# 2-MCU.net
KiCad netlist of a schematic drawn in Altium Designer
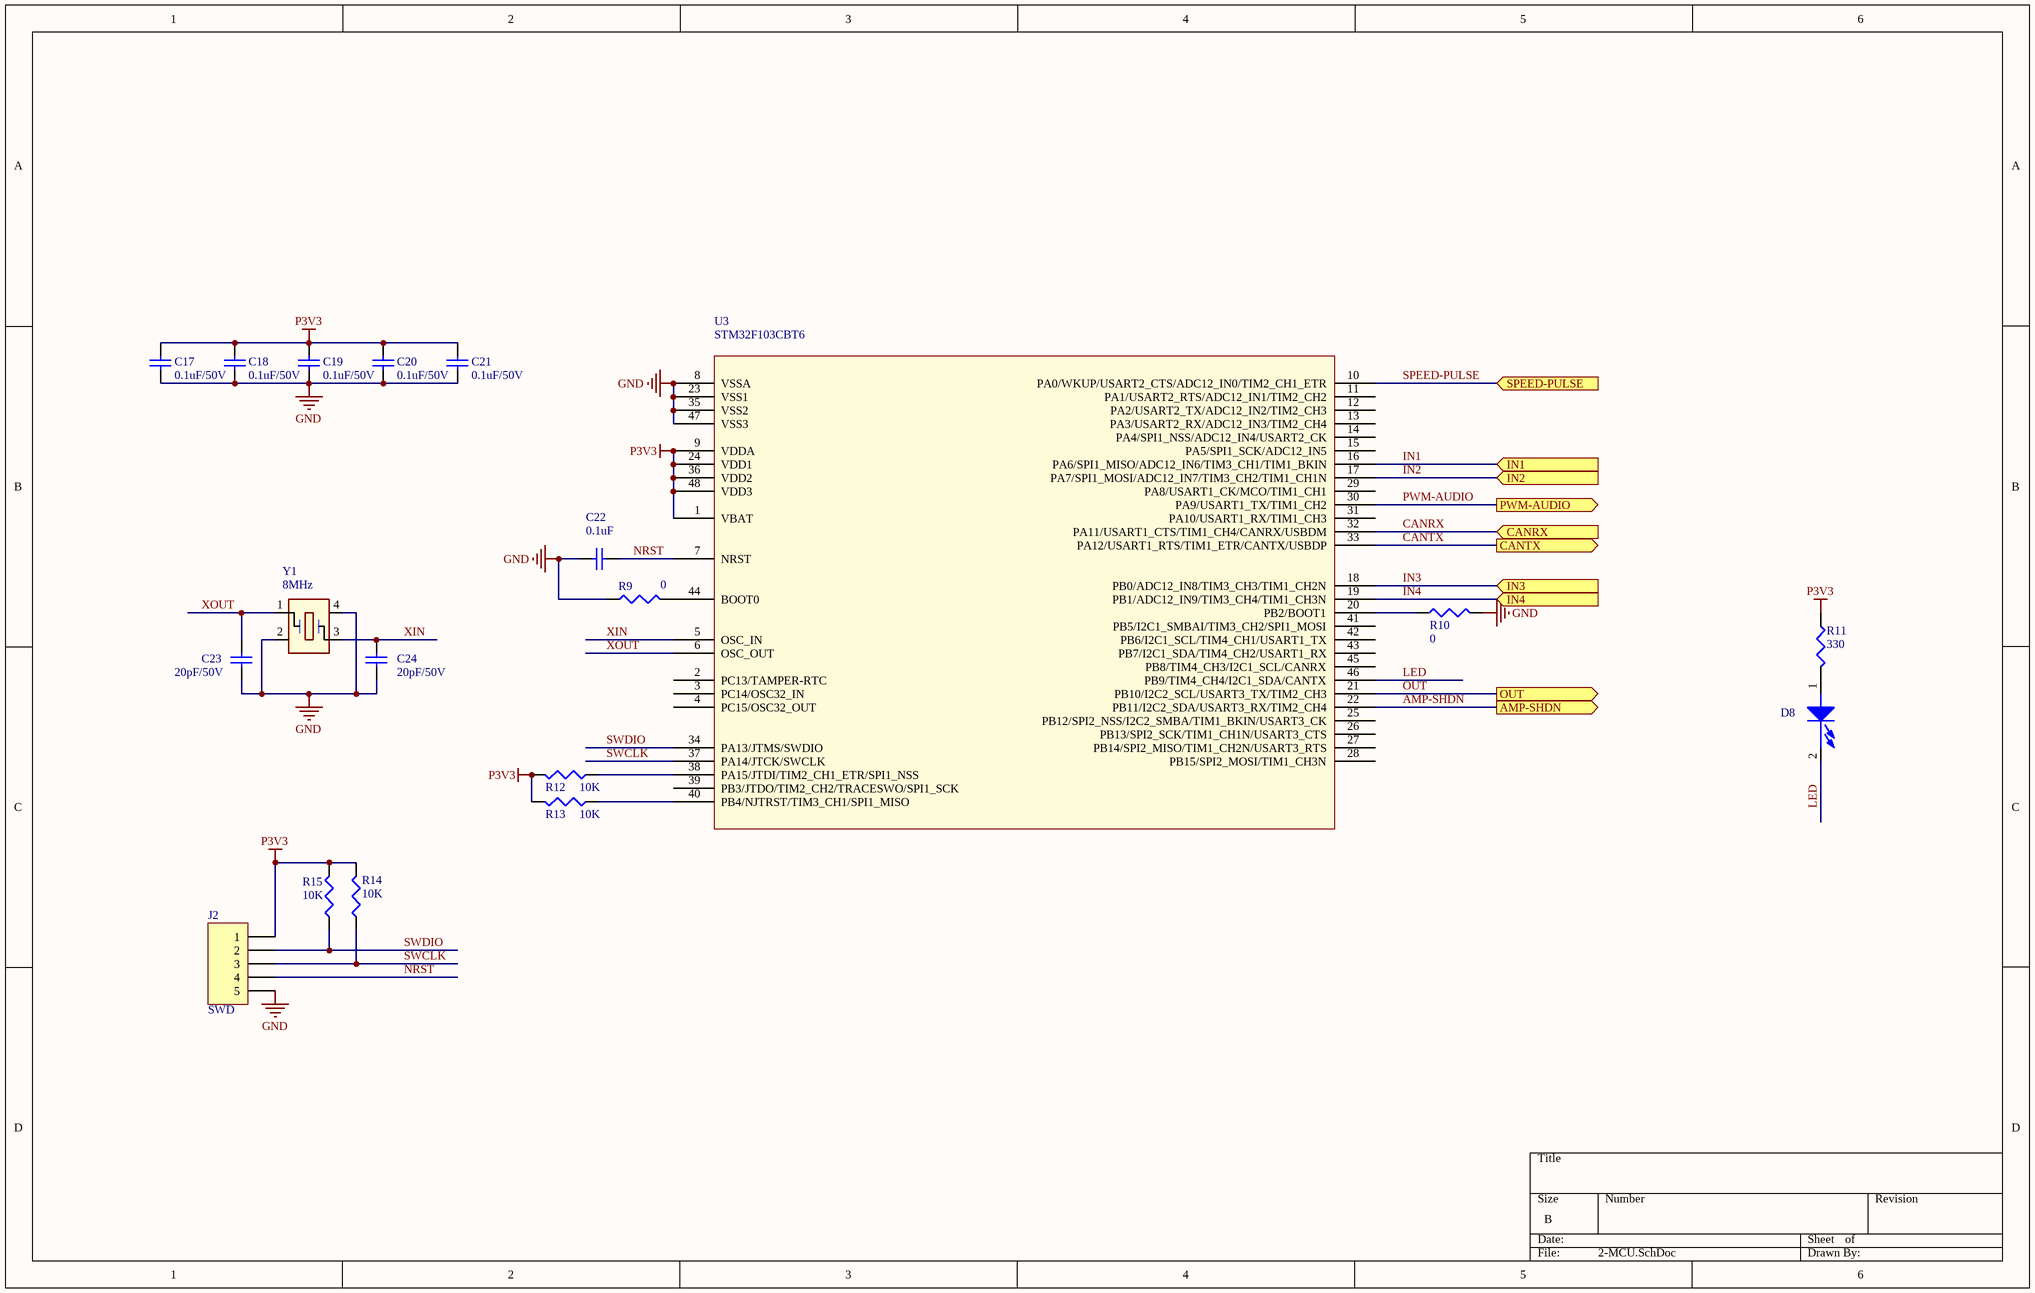
[diagram p0: 2-MCU.SchDoc]

(export (version "E")
  (design (tool "Eeschema 10.0.6"))
  (components
    (comp (ref "C17")
      (value "0.1uF/50V")
      (footprint "0402")
      (description "Capacitor")
      (fields (field (name "PUBLISHER") "Altium Limited"))
      (libsource (lib "Miscellaneous Devices") (part "Cap"))
    )
    (comp (ref "C18")
      (value "0.1uF/50V")
      (footprint "0402")
      (description "Capacitor")
      (fields (field (name "PUBLISHER") "Altium Limited"))
      (libsource (lib "Miscellaneous Devices") (part "Cap"))
    )
    (comp (ref "C19")
      (value "0.1uF/50V")
      (footprint "0402")
      (description "Capacitor")
      (fields (field (name "PUBLISHER") "Altium Limited"))
      (libsource (lib "Miscellaneous Devices") (part "Cap"))
    )
    (comp (ref "C20")
      (value "0.1uF/50V")
      (footprint "0402")
      (description "Capacitor")
      (fields (field (name "PUBLISHER") "Altium Limited"))
      (libsource (lib "Miscellaneous Devices") (part "Cap"))
    )
    (comp (ref "C21")
      (value "0.1uF/50V")
      (footprint "0402")
      (description "Capacitor")
      (fields (field (name "PUBLISHER") "Altium Limited"))
      (libsource (lib "Miscellaneous Devices") (part "Cap"))
    )
    (comp (ref "C22")
      (value "0.1uF")
      (footprint "0402")
      (description "Capacitor")
      (fields (field (name "PUBLISHER") "Altium Limited"))
      (libsource (lib "Miscellaneous Devices") (part "Cap"))
    )
    (comp (ref "C23")
      (value "20pF/50V")
      (footprint "0402")
      (description "Capacitor")
      (fields (field (name "PUBLISHER") "Altium Limited"))
      (libsource (lib "Miscellaneous Devices") (part "Cap"))
    )
    (comp (ref "C24")
      (value "20pF/50V")
      (footprint "0402")
      (description "Capacitor")
      (fields (field (name "PUBLISHER") "Altium Limited"))
      (libsource (lib "Miscellaneous Devices") (part "Cap"))
    )
    (comp (ref "D8") (value "LED GREEN") (footprint "LED0603") (libsource (lib "*") (part "LN01401_1")))
    (comp (ref "J2")
      (value "SWD")
      (footprint "HDR1X5")
      (description "Header, 5-Pin")
      (fields (field (name "PUBLISHER") "Altium Limited"))
      (libsource (lib "Miscellaneous Connectors") (part "Header 5"))
    )
    (comp (ref "R9")
      (value "0")
      (footprint "0402")
      (description "Resistor")
      (fields (field (name "PUBLISHER") "Altium Limited"))
      (libsource (lib "Miscellaneous Devices") (part "Res3"))
    )
    (comp (ref "R10")
      (value "0")
      (footprint "0402")
      (description "Resistor")
      (fields (field (name "PUBLISHER") "Altium Limited"))
      (libsource (lib "Miscellaneous Devices") (part "Res3"))
    )
    (comp (ref "R11") (value "330") (footprint "0402") (libsource (lib "*") (part "CR16-1003FM")))
    (comp (ref "R12")
      (value "10K")
      (footprint "0402")
      (description "Resistor")
      (fields (field (name "PUBLISHER") "Altium Limited"))
      (libsource (lib "Miscellaneous Devices") (part "Res3"))
    )
    (comp (ref "R13")
      (value "10K")
      (footprint "0402")
      (description "Resistor")
      (fields (field (name "PUBLISHER") "Altium Limited"))
      (libsource (lib "Miscellaneous Devices") (part "Res3"))
    )
    (comp (ref "R14")
      (value "10K")
      (footprint "0402")
      (description "Resistor")
      (fields (field (name "PUBLISHER") "Altium Limited"))
      (libsource (lib "Miscellaneous Devices") (part "Res3"))
    )
    (comp (ref "R15")
      (value "10K")
      (footprint "0402")
      (description "Resistor")
      (fields (field (name "PUBLISHER") "Altium Limited"))
      (libsource (lib "Miscellaneous Devices") (part "Res3"))
    )
    (comp (ref "U3")
      (value "STM32F103CBT6")
      (footprint "LQFP48")
      (libsource (lib "Schlib") (part "STM32F103CX-LQFP48"))
    )
    (comp (ref "Y1")
      (value "8MHz")
      (footprint "XTAL4_SX_3225")
      (description "XTAL 24MHZ -- 3.2X2.5MM SMT")
      (libsource (lib "*") (part "XTAL_13Y_A"))
    )
  )
  (nets
    (net (code "1") (name "/AMP-SHDN") (class "Default")
      (node (ref "U3") (pin "22") (pinfunction "PB11/I2C2_SDA/USART3_RX/TIM2_CH4_22") (pintype "passive"))
    )
    (net (code "2") (name "/CANRX") (class "Default")
      (node (ref "U3") (pin "32") (pinfunction "PA11/USART1_CTS/TIM1_CH4/CANRX/USBDM_32") (pintype "passive"))
    )
    (net (code "3") (name "/CANTX") (class "Default")
      (node (ref "U3") (pin "33") (pinfunction "PA12/USART1_RTS/TIM1_ETR/CANTX/USBDP_33") (pintype "passive"))
    )
    (net (code "4") (name "/IN1") (class "Default")
      (node (ref "U3") (pin "16") (pinfunction "PA6/SPI1_MISO/ADC12_IN6/TIM3_CH1/TIM1_BKIN_16") (pintype "passive"))
    )
    (net (code "5") (name "/IN2") (class "Default")
      (node (ref "U3") (pin "17") (pinfunction "PA7/SPI1_MOSI/ADC12_IN7/TIM3_CH2/TIM1_CH1N_17") (pintype "passive"))
    )
    (net (code "6") (name "/IN3") (class "Default")
      (node (ref "U3") (pin "18") (pinfunction "PB0/ADC12_IN8/TIM3_CH3/TIM1_CH2N_18") (pintype "passive"))
    )
    (net (code "7") (name "/IN4") (class "Default")
      (node (ref "U3") (pin "19") (pinfunction "PB1/ADC12_IN9/TIM3_CH4/TIM1_CH3N_19") (pintype "passive"))
    )
    (net (code "8") (name "/LED") (class "Default")
      (node (ref "D8") (pin "2") (pinfunction "CATHODE_2") (pintype "passive"))
      (node (ref "U3") (pin "46") (pinfunction "PB9/TIM4_CH4/I2C1_SDA/CANTX_46") (pintype "passive"))
    )
    (net (code "9") (name "/NRST") (class "Default")
      (node (ref "C22") (pin "2") (pinfunction "2_2") (pintype "passive"))
      (node (ref "J2") (pin "4") (pinfunction "4_4") (pintype "passive"))
      (node (ref "U3") (pin "7") (pinfunction "NRST_7") (pintype "passive"))
    )
    (net (code "10") (name "/OUT") (class "Default")
      (node (ref "U3") (pin "21") (pinfunction "PB10/I2C2_SCL/USART3_TX/TIM2_CH3_21") (pintype "passive"))
    )
    (net (code "11") (name "/PWM-AUDIO") (class "Default")
      (node (ref "U3") (pin "30") (pinfunction "PA9/USART1_TX/TIM1_CH2_30") (pintype "passive"))
    )
    (net (code "12") (name "/SPEED-PULSE") (class "Default")
      (node (ref "U3") (pin "10") (pinfunction "PA0/WKUP/USART2_CTS/ADC12_IN0/TIM2_CH1_ETR_10") (pintype "passive"))
    )
    (net (code "13") (name "/SWCLK") (class "Default")
      (node (ref "J2") (pin "3") (pinfunction "3_3") (pintype "passive"))
      (node (ref "R14") (pin "1") (pinfunction "1_1") (pintype "passive"))
      (node (ref "U3") (pin "37") (pinfunction "PA14/JTCK/SWCLK_37") (pintype "passive"))
    )
    (net (code "14") (name "/SWDIO") (class "Default")
      (node (ref "J2") (pin "2") (pinfunction "2_2") (pintype "passive"))
      (node (ref "R15") (pin "1") (pinfunction "1_1") (pintype "passive"))
      (node (ref "U3") (pin "34") (pinfunction "PA13/JTMS/SWDIO_34") (pintype "passive"))
    )
    (net (code "15") (name "/XIN") (class "Default")
      (node (ref "C24") (pin "1") (pinfunction "1_1") (pintype "passive"))
      (node (ref "U3") (pin "5") (pinfunction "OSC_IN_5") (pintype "passive"))
      (node (ref "Y1") (pin "3") (pinfunction "3_3") (pintype "passive"))
    )
    (net (code "16") (name "/XOUT") (class "Default")
      (node (ref "C23") (pin "1") (pinfunction "1_1") (pintype "passive"))
      (node (ref "U3") (pin "6") (pinfunction "OSC_OUT_6") (pintype "passive"))
      (node (ref "Y1") (pin "1") (pinfunction "1_1") (pintype "passive"))
    )
    (net (code "17") (name "GND") (class "Default")
      (node (ref "C17") (pin "1") (pinfunction "1_1") (pintype "passive"))
      (node (ref "C18") (pin "1") (pinfunction "1_1") (pintype "passive"))
      (node (ref "C19") (pin "1") (pinfunction "1_1") (pintype "passive"))
      (node (ref "C20") (pin "1") (pinfunction "1_1") (pintype "passive"))
      (node (ref "C21") (pin "1") (pinfunction "1_1") (pintype "passive"))
      (node (ref "C22") (pin "1") (pinfunction "1_1") (pintype "passive"))
      (node (ref "C23") (pin "2") (pinfunction "2_2") (pintype "passive"))
      (node (ref "C24") (pin "2") (pinfunction "2_2") (pintype "passive"))
      (node (ref "J2") (pin "5") (pinfunction "5_5") (pintype "passive"))
      (node (ref "R10") (pin "2") (pinfunction "2_2") (pintype "passive"))
      (node (ref "R9") (pin "1") (pinfunction "1_1") (pintype "passive"))
      (node (ref "U3") (pin "23") (pinfunction "VSS1_23") (pintype "passive"))
      (node (ref "U3") (pin "35") (pinfunction "VSS2_35") (pintype "passive"))
      (node (ref "U3") (pin "47") (pinfunction "VSS3_47") (pintype "passive"))
      (node (ref "U3") (pin "8") (pinfunction "VSSA_8") (pintype "passive"))
      (node (ref "Y1") (pin "2") (pinfunction "2_2") (pintype "passive"))
      (node (ref "Y1") (pin "4") (pinfunction "4_4") (pintype "passive"))
    )
    (net (code "18") (name "Net-(D8-ANODE)") (class "Default")
      (node (ref "D8") (pin "1") (pinfunction "ANODE_1") (pintype "passive"))
      (node (ref "R11") (pin "2") (pinfunction "2_2") (pintype "passive"))
    )
    (net (code "19") (name "Net-(U3-BOOT0)") (class "Default")
      (node (ref "R9") (pin "2") (pinfunction "2_2") (pintype "passive"))
      (node (ref "U3") (pin "44") (pinfunction "BOOT0_44") (pintype "passive"))
    )
    (net (code "20") (name "Net-(U3-PA15{slash}JTDI{slash}TIM2_CH1_ETR{slash}SPI1_NSS)") (class "Default")
      (node (ref "R12") (pin "1") (pinfunction "1_1") (pintype "passive"))
      (node (ref "U3") (pin "38") (pinfunction "PA15/JTDI/TIM2_CH1_ETR/SPI1_NSS_38") (pintype "passive"))
    )
    (net (code "21") (name "Net-(U3-PB2{slash}BOOT1)") (class "Default")
      (node (ref "R10") (pin "1") (pinfunction "1_1") (pintype "passive"))
      (node (ref "U3") (pin "20") (pinfunction "PB2/BOOT1_20") (pintype "passive"))
    )
    (net (code "22") (name "Net-(U3-PB4{slash}NJTRST{slash}TIM3_CH1{slash}SPI1_MISO)") (class "Default")
      (node (ref "R13") (pin "1") (pinfunction "1_1") (pintype "passive"))
      (node (ref "U3") (pin "40") (pinfunction "PB4/NJTRST/TIM3_CH1/SPI1_MISO_40") (pintype "passive"))
    )
    (net (code "23") (name "P3V3") (class "Default")
      (node (ref "C17") (pin "2") (pinfunction "2_2") (pintype "passive"))
      (node (ref "C18") (pin "2") (pinfunction "2_2") (pintype "passive"))
      (node (ref "C19") (pin "2") (pinfunction "2_2") (pintype "passive"))
      (node (ref "C20") (pin "2") (pinfunction "2_2") (pintype "passive"))
      (node (ref "C21") (pin "2") (pinfunction "2_2") (pintype "passive"))
      (node (ref "J2") (pin "1") (pinfunction "1_1") (pintype "passive"))
      (node (ref "R11") (pin "1") (pinfunction "1_1") (pintype "passive"))
      (node (ref "R12") (pin "2") (pinfunction "2_2") (pintype "passive"))
      (node (ref "R13") (pin "2") (pinfunction "2_2") (pintype "passive"))
      (node (ref "R14") (pin "2") (pinfunction "2_2") (pintype "passive"))
      (node (ref "R15") (pin "2") (pinfunction "2_2") (pintype "passive"))
      (node (ref "U3") (pin "1") (pinfunction "VBAT_1") (pintype "passive"))
      (node (ref "U3") (pin "24") (pinfunction "VDD1_24") (pintype "passive"))
      (node (ref "U3") (pin "36") (pinfunction "VDD2_36") (pintype "passive"))
      (node (ref "U3") (pin "48") (pinfunction "VDD3_48") (pintype "passive"))
      (node (ref "U3") (pin "9") (pinfunction "VDDA_9") (pintype "passive"))
    )
    (net (code "24") (name "unconnected-(U3-PA1{slash}USART2_RTS{slash}ADC12_IN1{slash}TIM2_CH2-Pad11)") (class "Default")
      (node (ref "U3") (pin "11") (pinfunction "PA1/USART2_RTS/ADC12_IN1/TIM2_CH2_11") (pintype "passive"))
    )
    (net (code "25") (name "unconnected-(U3-PA2{slash}USART2_TX{slash}ADC12_IN2{slash}TIM2_CH3-Pad12)") (class "Default")
      (node (ref "U3") (pin "12") (pinfunction "PA2/USART2_TX/ADC12_IN2/TIM2_CH3_12") (pintype "passive"))
    )
    (net (code "26") (name "unconnected-(U3-PA3{slash}USART2_RX{slash}ADC12_IN3{slash}TIM2_CH4-Pad13)") (class "Default")
      (node (ref "U3") (pin "13") (pinfunction "PA3/USART2_RX/ADC12_IN3/TIM2_CH4_13") (pintype "passive"))
    )
    (net (code "27") (name "unconnected-(U3-PA4{slash}SPI1_NSS{slash}ADC12_IN4{slash}USART2_CK-Pad14)") (class "Default")
      (node (ref "U3") (pin "14") (pinfunction "PA4/SPI1_NSS/ADC12_IN4/USART2_CK_14") (pintype "passive"))
    )
    (net (code "28") (name "unconnected-(U3-PA5{slash}SPI1_SCK{slash}ADC12_IN5-Pad15)") (class "Default")
      (node (ref "U3") (pin "15") (pinfunction "PA5/SPI1_SCK/ADC12_IN5_15") (pintype "passive"))
    )
    (net (code "29") (name "unconnected-(U3-PA8{slash}USART1_CK{slash}MCO{slash}TIM1_CH1-Pad29)") (class "Default")
      (node (ref "U3") (pin "29") (pinfunction "PA8/USART1_CK/MCO/TIM1_CH1_29") (pintype "passive"))
    )
    (net (code "30") (name "unconnected-(U3-PA10{slash}USART1_RX{slash}TIM1_CH3-Pad31)") (class "Default")
      (node (ref "U3") (pin "31") (pinfunction "PA10/USART1_RX/TIM1_CH3_31") (pintype "passive"))
    )
    (net (code "31") (name "unconnected-(U3-PB3{slash}JTDO{slash}TIM2_CH2{slash}TRACESWO{slash}SPI1_SCK-Pad39)") (class "Default")
      (node (ref "U3") (pin "39") (pinfunction "PB3/JTDO/TIM2_CH2/TRACESWO/SPI1_SCK_39") (pintype "passive"))
    )
    (net (code "32") (name "unconnected-(U3-PB5{slash}I2C1_SMBAI{slash}TIM3_CH2{slash}SPI1_MOSI-Pad41)") (class "Default")
      (node (ref "U3") (pin "41") (pinfunction "PB5/I2C1_SMBAI/TIM3_CH2/SPI1_MOSI_41") (pintype "passive"))
    )
    (net (code "33") (name "unconnected-(U3-PB6{slash}I2C1_SCL{slash}TIM4_CH1{slash}USART1_TX-Pad42)") (class "Default")
      (node (ref "U3") (pin "42") (pinfunction "PB6/I2C1_SCL/TIM4_CH1/USART1_TX_42") (pintype "passive"))
    )
    (net (code "34") (name "unconnected-(U3-PB7{slash}I2C1_SDA{slash}TIM4_CH2{slash}USART1_RX-Pad43)") (class "Default")
      (node (ref "U3") (pin "43") (pinfunction "PB7/I2C1_SDA/TIM4_CH2/USART1_RX_43") (pintype "passive"))
    )
    (net (code "35") (name "unconnected-(U3-PB8{slash}TIM4_CH3{slash}I2C1_SCL{slash}CANRX-Pad45)") (class "Default")
      (node (ref "U3") (pin "45") (pinfunction "PB8/TIM4_CH3/I2C1_SCL/CANRX_45") (pintype "passive"))
    )
    (net (code "36") (name "unconnected-(U3-PB12{slash}SPI2_NSS{slash}I2C2_SMBA{slash}TIM1_BKIN{slash}USART3_CK-Pad25)") (class "Default")
      (node (ref "U3") (pin "25") (pinfunction "PB12/SPI2_NSS/I2C2_SMBA/TIM1_BKIN/USART3_CK_25") (pintype "passive"))
    )
    (net (code "37") (name "unconnected-(U3-PB13{slash}SPI2_SCK{slash}TIM1_CH1N{slash}USART3_CTS-Pad26)") (class "Default")
      (node (ref "U3") (pin "26") (pinfunction "PB13/SPI2_SCK/TIM1_CH1N/USART3_CTS_26") (pintype "passive"))
    )
    (net (code "38") (name "unconnected-(U3-PB14{slash}SPI2_MISO{slash}TIM1_CH2N{slash}USART3_RTS-Pad27)") (class "Default")
      (node (ref "U3") (pin "27") (pinfunction "PB14/SPI2_MISO/TIM1_CH2N/USART3_RTS_27") (pintype "passive"))
    )
    (net (code "39") (name "unconnected-(U3-PB15{slash}SPI2_MOSI{slash}TIM1_CH3N-Pad28)") (class "Default")
      (node (ref "U3") (pin "28") (pinfunction "PB15/SPI2_MOSI/TIM1_CH3N_28") (pintype "passive"))
    )
    (net (code "40") (name "unconnected-(U3-PC13{slash}TAMPER-RTC-Pad2)") (class "Default")
      (node (ref "U3") (pin "2") (pinfunction "PC13/TAMPER-RTC_2") (pintype "passive"))
    )
    (net (code "41") (name "unconnected-(U3-PC14{slash}OSC32_IN-Pad3)") (class "Default")
      (node (ref "U3") (pin "3") (pinfunction "PC14/OSC32_IN_3") (pintype "passive"))
    )
    (net (code "42") (name "unconnected-(U3-PC15{slash}OSC32_OUT-Pad4)") (class "Default")
      (node (ref "U3") (pin "4") (pinfunction "PC15/OSC32_OUT_4") (pintype "passive"))
    )
  )
)
